# LM2576_Buckconverter.net
KiCad netlist of a schematic drawn in Altium Designer
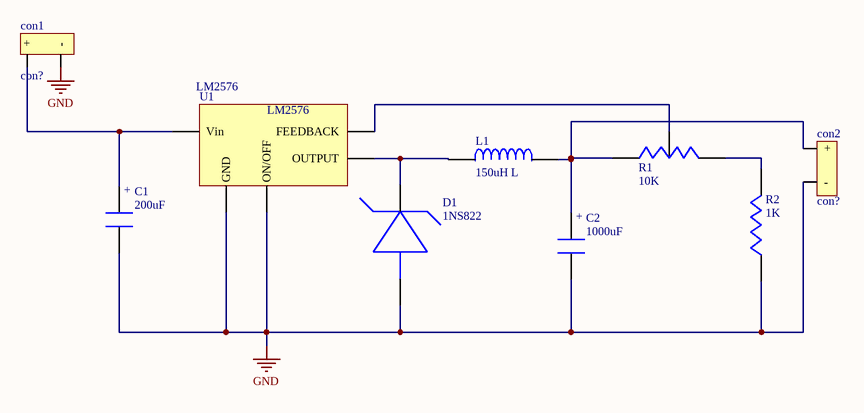
[diagram p0: LM2576_Buckconverter.SchDoc]

(export (version "E")
  (design (tool "Eeschema 10.0.6"))
  (components
    (comp (ref "C1")
      (value "200uF")
      (footprint "220uF Capacitor")
      (libsource (lib "LM2576_Buckconverter") (part "Electrolytic Cap"))
    )
    (comp (ref "C2")
      (value "1000uF")
      (footprint "1000UF CAP")
      (libsource (lib "LM2576_Buckconverter") (part "Electrolytic Cap"))
    )
    (comp (ref "con1") (value "con?") (footprint "2pin") (libsource (lib "") (part "2pinconnector_1")))
    (comp (ref "con2")
      (value "con?")
      (footprint "2pin")
      (libsource (lib "LM2576_Buckconverter") (part "2pinconnector"))
    )
    (comp (ref "D1")
      (value "1NS822")
      (footprint "1N5822")
      (libsource (lib "LM2576_Buckconverter") (part "1NS822"))
    )
    (comp (ref "L1")
      (value "150uH L")
      (footprint "150uH Inductor")
      (libsource (lib "LM2576_Buckconverter") (part "150uH L"))
    )
    (comp (ref "R1")
      (value "10K")
      (footprint "10K POT")
      (libsource (lib "LM2576_Buckconverter") (part "Variable Resistor"))
    )
    (comp (ref "R2")
      (value "1K")
      (footprint "1K 1206 Resistor")
      (libsource (lib "LM2576_Buckconverter") (part "Resistor"))
    )
    (comp (ref "U1")
      (value "LM2576")
      (footprint "LM2576-TO63-S")
      (libsource (lib "LM2576_Buckconverter") (part "LM2576"))
    )
  )
  (nets
    (net (code "1") (name "GND") (class "Default")
      (node (ref "C1") (pin "2") (pinfunction "2_2") (pintype "passive"))
      (node (ref "C2") (pin "2") (pinfunction "2_2") (pintype "passive"))
      (node (ref "D1") (pin "2") (pinfunction "2_2") (pintype "passive"))
      (node (ref "R2") (pin "1") (pinfunction "1_1") (pintype "passive"))
      (node (ref "U1") (pin "3") (pinfunction "GND_3") (pintype "passive"))
      (node (ref "U1") (pin "5") (pinfunction "ON/OFF_5") (pintype "passive"))
      (node (ref "con1") (pin "2") (pinfunction "-_2") (pintype "passive"))
      (node (ref "con2") (pin "2") (pinfunction "-_2") (pintype "passive"))
    )
    (net (code "2") (name "Net-(R1-Pad2)") (class "Default")
      (node (ref "R1") (pin "2") (pinfunction "2_2") (pintype "passive"))
      (node (ref "R2") (pin "2") (pinfunction "2_2") (pintype "passive"))
    )
    (net (code "3") (name "Net-(U1-FEEDBACK)") (class "Default")
      (node (ref "R1") (pin "3") (pinfunction "3_3") (pintype "passive"))
      (node (ref "U1") (pin "4") (pinfunction "FEEDBACK_4") (pintype "passive"))
    )
    (net (code "4") (name "Net-(U1-OUTPUT)") (class "Default")
      (node (ref "D1") (pin "1") (pinfunction "1_1") (pintype "passive"))
      (node (ref "L1") (pin "1") (pinfunction "1_1") (pintype "passive"))
      (node (ref "U1") (pin "2") (pinfunction "OUTPUT_2") (pintype "passive"))
    )
    (net (code "5") (name "Net-(U1-Vin)") (class "Default")
      (node (ref "C1") (pin "1") (pinfunction "1_1") (pintype "passive"))
      (node (ref "U1") (pin "1") (pinfunction "Vin_1") (pintype "passive"))
      (node (ref "con1") (pin "1") (pinfunction "+_1") (pintype "passive"))
    )
    (net (code "6") (name "Net-(con2-+)") (class "Default")
      (node (ref "C2") (pin "1") (pinfunction "1_1") (pintype "passive"))
      (node (ref "L1") (pin "2") (pinfunction "2_2") (pintype "passive"))
      (node (ref "R1") (pin "1") (pinfunction "1_1") (pintype "passive"))
      (node (ref "con2") (pin "1") (pinfunction "+_1") (pintype "passive"))
    )
  )
)
